# SparkFun_LiPo-Charger-Basic-MiniUSB.net
KiCad netlist of a schematic drawn in EAGLE
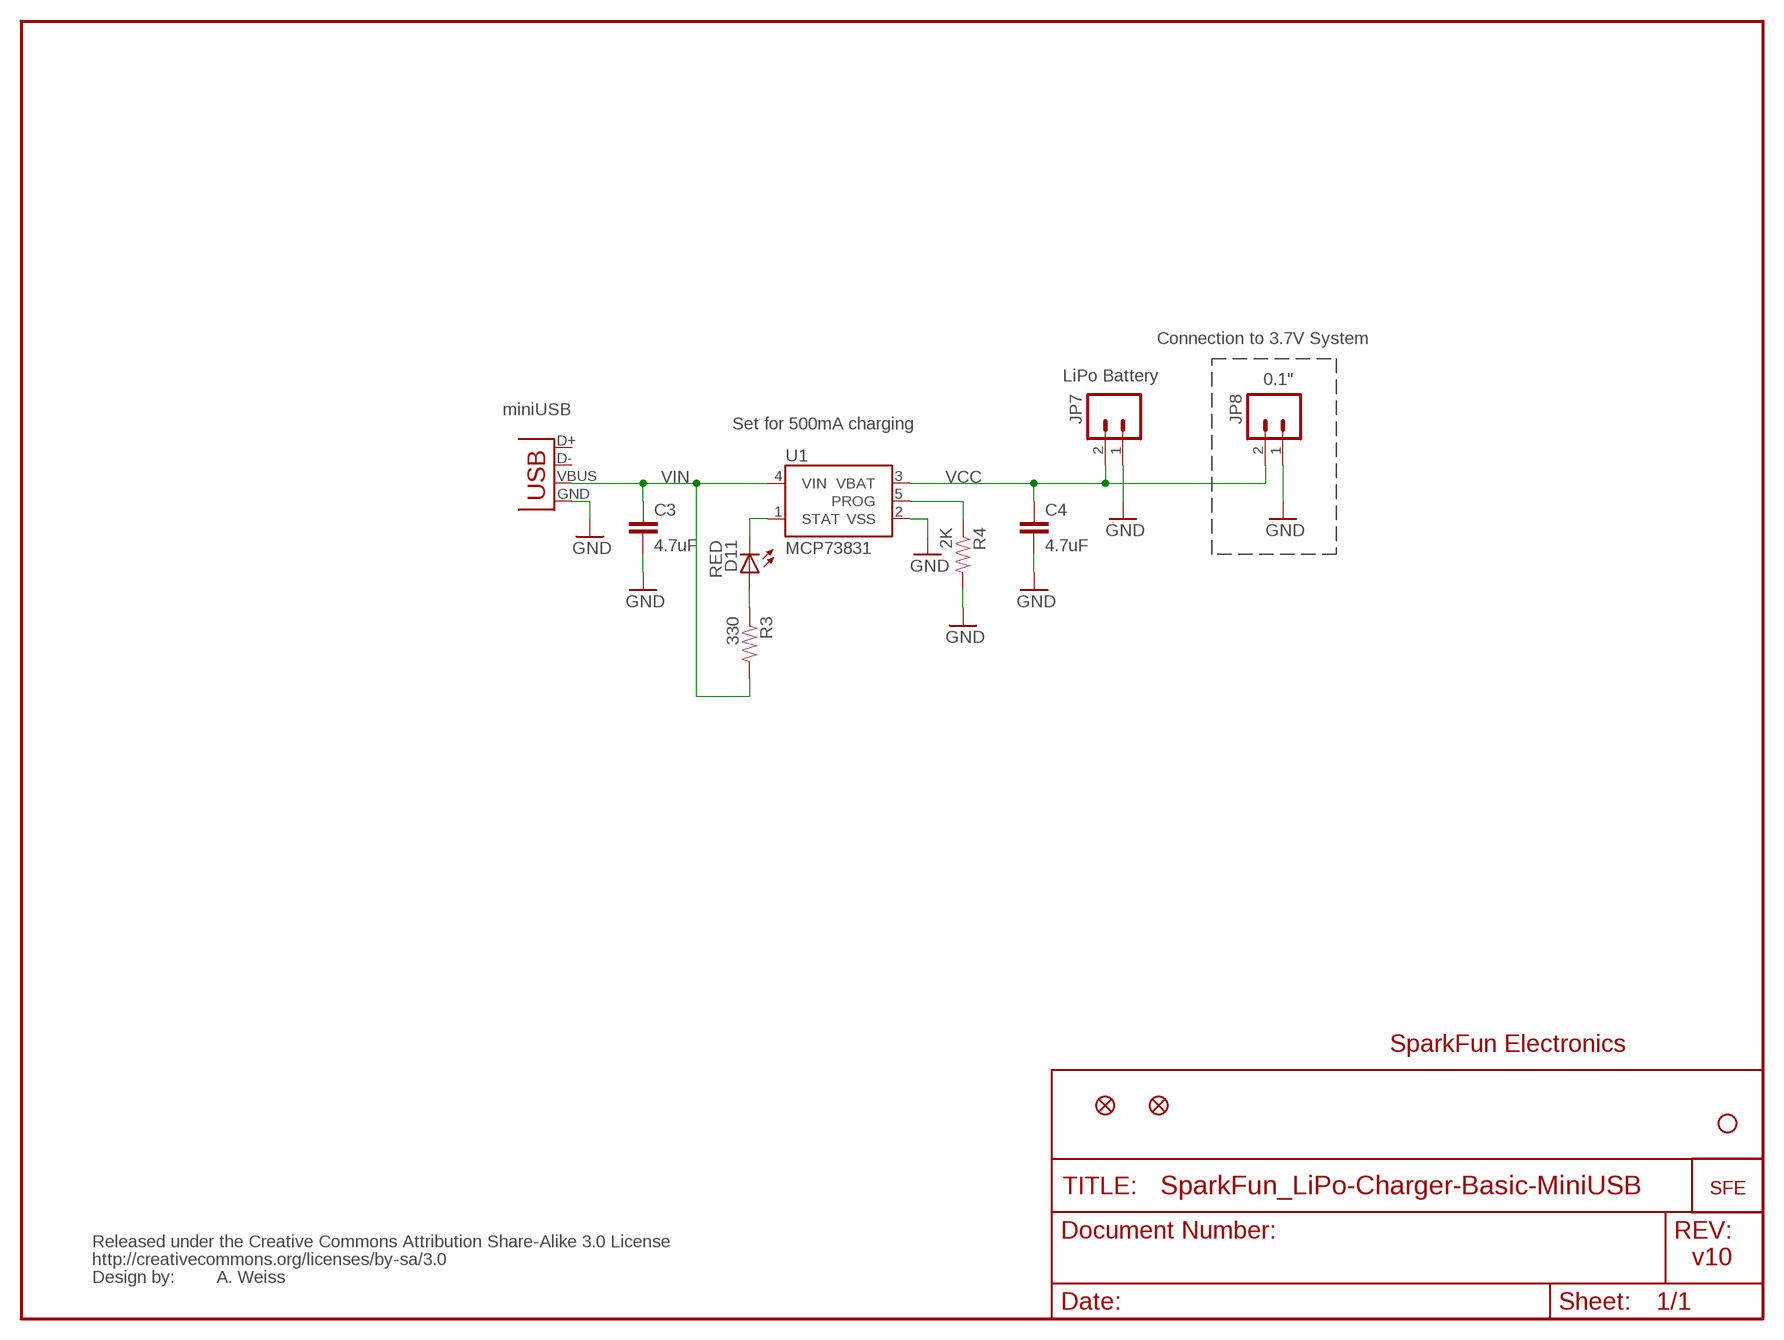
[diagram p0: schematic, sheet 1]

(export (version "E")
  (design (tool "Eeschema 10.0.6"))
  (components
    (comp (ref "C3")
      (value "4.7uF")
      (footprint "eagle-import:0402-CAP")
      (libsource (lib "eagle-import") (part "CAP0402-CAP"))
    )
    (comp (ref "C4")
      (value "4.7uF")
      (footprint "eagle-import:0402-CAP")
      (libsource (lib "eagle-import") (part "CAP0402-CAP"))
    )
    (comp (ref "D11")
      (value "RED")
      (footprint "eagle-import:LED-0603")
      (libsource (lib "eagle-import") (part "LED0603"))
    )
    (comp (ref "JP1")
      (value "LOGO-SFESK")
      (footprint "eagle-import:SFE-LOGO-FLAME")
      (libsource (lib "eagle-import") (part "LOGO-SFESK"))
    )
    (comp (ref "JP2")
      (value "STAND-OFF")
      (footprint "eagle-import:STAND-OFF")
      (libsource (lib "eagle-import") (part "STAND-OFF"))
    )
    (comp (ref "JP3")
      (value "FIDUCIAL1X2")
      (footprint "eagle-import:FIDUCIAL-1X2")
      (libsource (lib "eagle-import") (part "FIDUCIAL1X2"))
    )
    (comp (ref "JP4")
      (value "FIDUCIAL1X2")
      (footprint "eagle-import:FIDUCIAL-1X2")
      (libsource (lib "eagle-import") (part "FIDUCIAL1X2"))
    )
    (comp (ref "JP7")
      (value "LiPo Battery")
      (footprint "eagle-import:JST-2-SMD")
      (libsource (lib "eagle-import") (part "M02-JST-2MM-SMT"))
    )
    (comp (ref "JP8")
      (value "M02PTH")
      (footprint "eagle-import:1X02")
      (libsource (lib "eagle-import") (part "M02PTH"))
    )
    (comp (ref "R3")
      (value "330")
      (footprint "eagle-import:0402-RES")
      (libsource (lib "eagle-import") (part "RESISTOR0402-RES"))
    )
    (comp (ref "R4")
      (value "2K")
      (footprint "eagle-import:0402-RES")
      (libsource (lib "eagle-import") (part "RESISTOR0402-RES"))
    )
    (comp (ref "U$1")
      (value "CREATIVE_COMMONS")
      (footprint "eagle-import:CREATIVE_COMMONS")
      (libsource (lib "eagle-import") (part "CREATIVE_COMMONS"))
    )
    (comp (ref "U1")
      (value "MCP73831")
      (footprint "eagle-import:SOT23-5")
      (libsource (lib "eagle-import") (part "MCP73831"))
    )
    (comp (ref "X1")
      (value "Micro USB")
      (footprint "eagle-import:USB-MINIB")
      (libsource (lib "eagle-import") (part "USBSMD"))
    )
  )
  (nets
    (net (code "1") (name "/VCC") (class "Default")
      (node (ref "C4") (pin "1") (pinfunction "1_1") (pintype "passive"))
      (node (ref "JP7") (pin "2") (pinfunction "2_2") (pintype "passive"))
      (node (ref "JP8") (pin "2") (pinfunction "2_2") (pintype "passive"))
      (node (ref "U1") (pin "3") (pinfunction "VBAT_3") (pintype "power_in"))
    )
    (net (code "2") (name "/VIN") (class "Default")
      (node (ref "C3") (pin "1") (pinfunction "1_1") (pintype "passive"))
      (node (ref "R3") (pin "2") (pinfunction "2_2") (pintype "passive"))
      (node (ref "U1") (pin "4") (pinfunction "VIN_4") (pintype "power_in"))
      (node (ref "X1") (pin "VBUS") (pinfunction "VBUS_VBUS") (pintype "bidirectional"))
    )
    (net (code "3") (name "GND") (class "Default")
      (node (ref "C3") (pin "2") (pinfunction "2_2") (pintype "passive"))
      (node (ref "C4") (pin "2") (pinfunction "2_2") (pintype "passive"))
      (node (ref "JP7") (pin "1") (pinfunction "1_1") (pintype "passive"))
      (node (ref "JP8") (pin "1") (pinfunction "1_1") (pintype "passive"))
      (node (ref "R4") (pin "2") (pinfunction "2_2") (pintype "passive"))
      (node (ref "U1") (pin "2") (pinfunction "VSS_2") (pintype "power_in"))
      (node (ref "X1") (pin "GND") (pinfunction "GND_GND") (pintype "bidirectional"))
    )
    (net (code "4") (name "Net-(D11-PadA)") (class "Default")
      (node (ref "D11") (pin "A") (pinfunction "A_A") (pintype "passive"))
      (node (ref "R3") (pin "1") (pinfunction "1_1") (pintype "passive"))
    )
    (net (code "5") (name "Net-(U1-PROG)") (class "Default")
      (node (ref "R4") (pin "1") (pinfunction "1_1") (pintype "passive"))
      (node (ref "U1") (pin "5") (pinfunction "PROG_5") (pintype "input"))
    )
    (net (code "6") (name "Net-(U1-STAT)") (class "Default")
      (node (ref "D11") (pin "C") (pinfunction "C_C") (pintype "passive"))
      (node (ref "U1") (pin "1") (pinfunction "STAT_1") (pintype "output"))
    )
    (net (code "7") (name "unconnected-(X1-PadD+)") (class "Default")
      (node (ref "X1") (pin "D+") (pinfunction "D+_D+") (pintype "bidirectional"))
    )
    (net (code "8") (name "unconnected-(X1-PadD-)") (class "Default")
      (node (ref "X1") (pin "D-") (pinfunction "D-_D-") (pintype "bidirectional"))
    )
  )
)
